# circuit.net
KiCad netlist of a schematic drawn in EAGLE
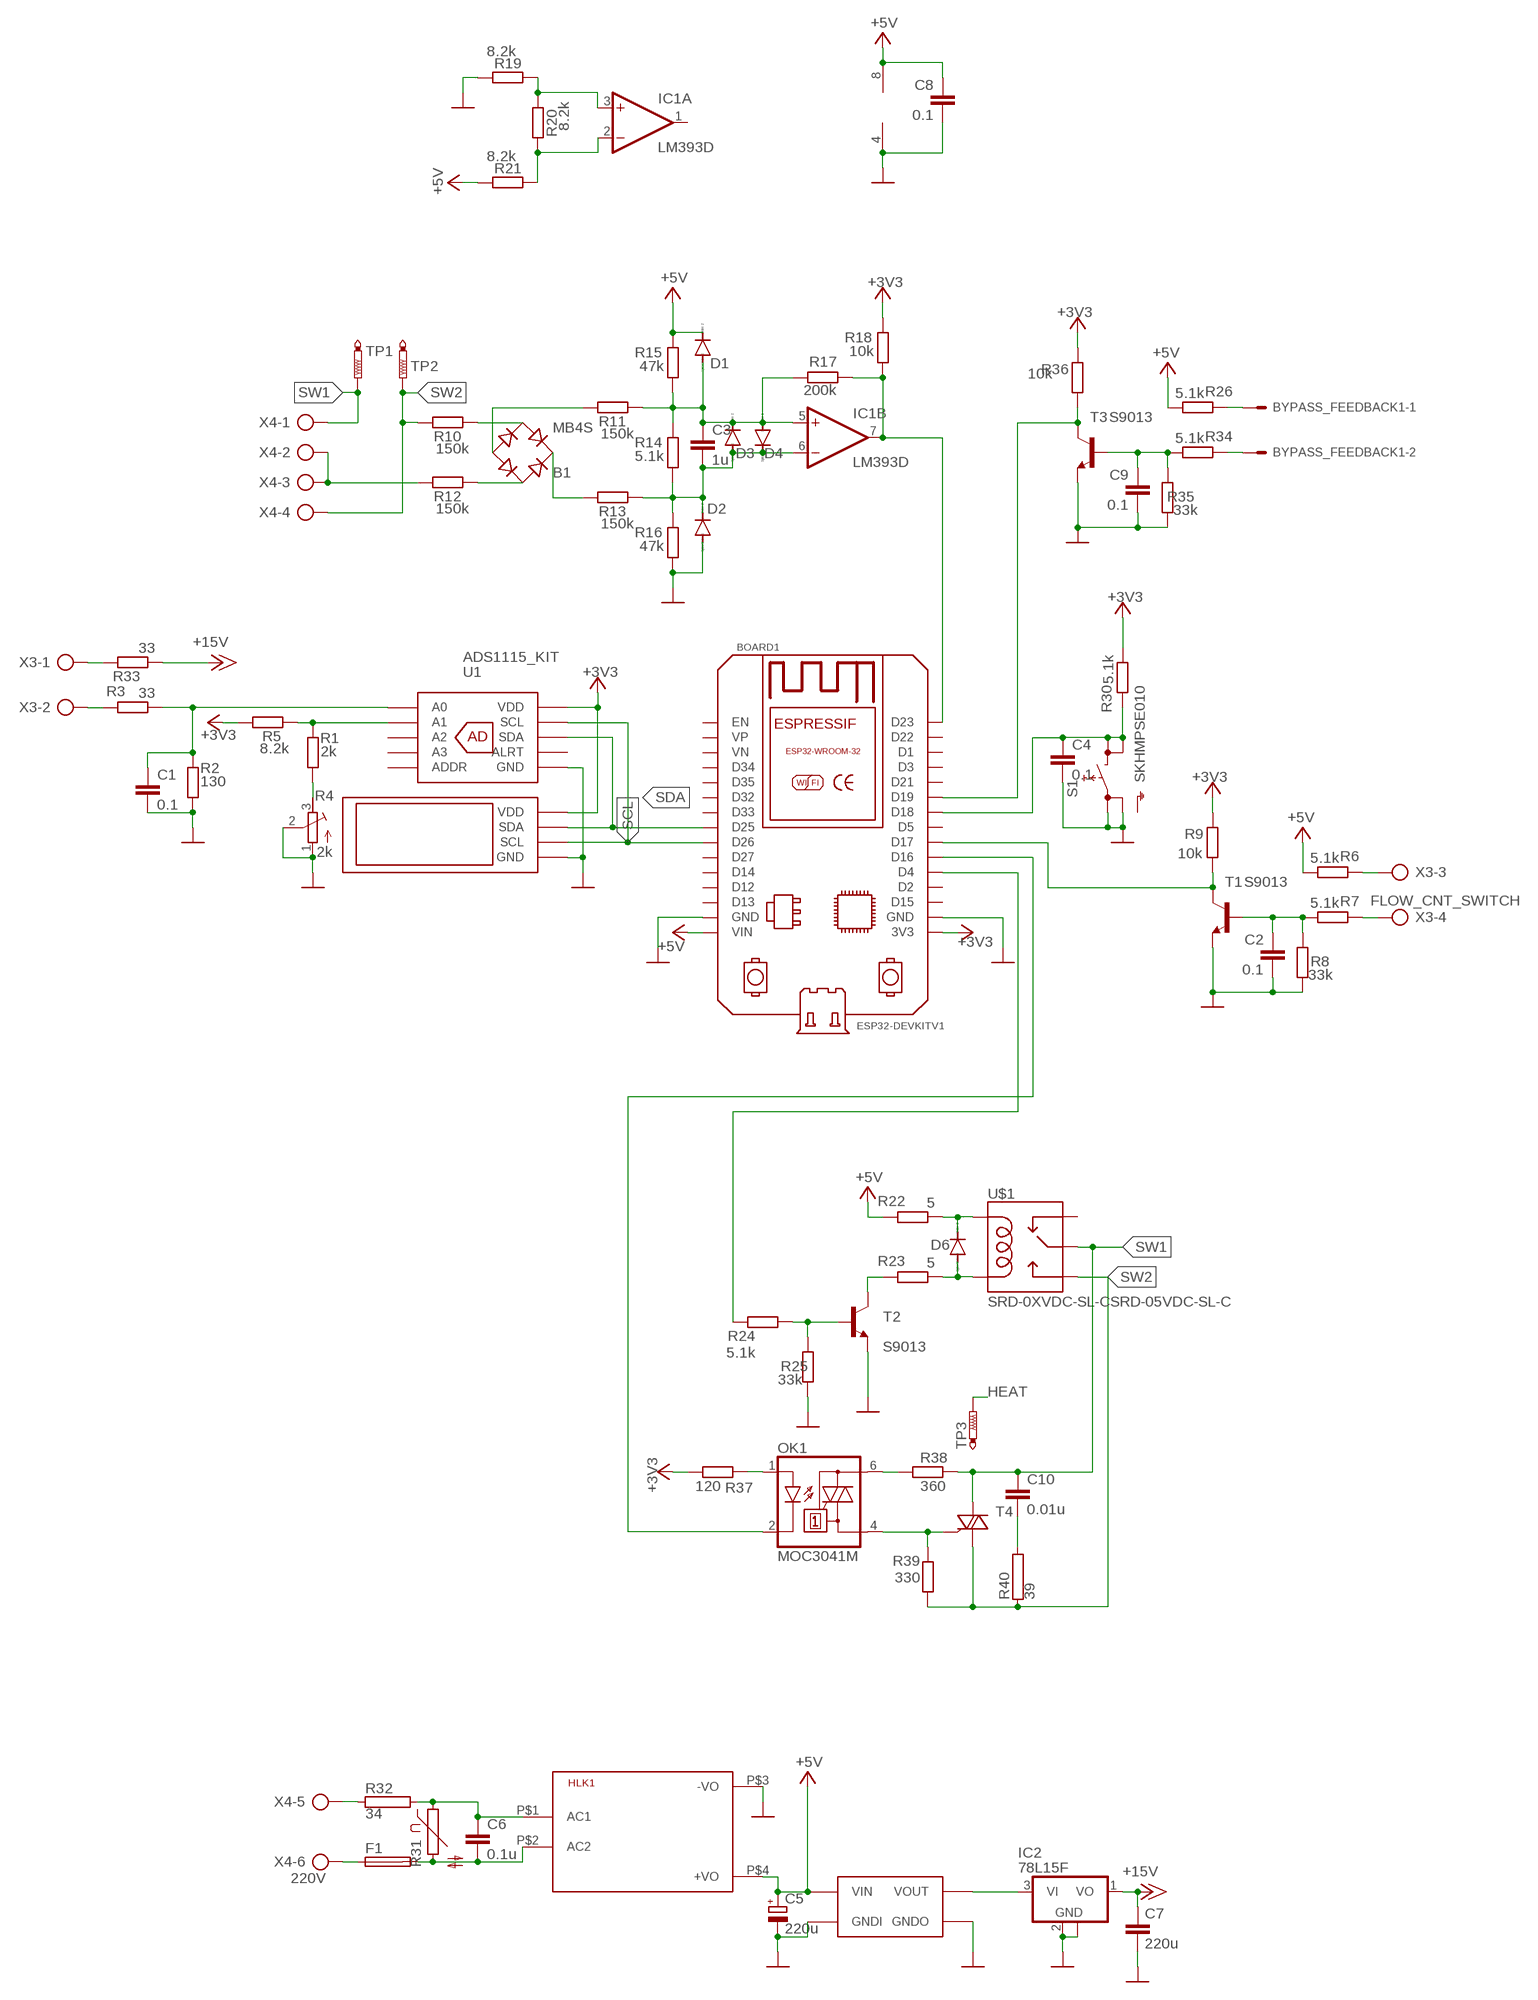
[diagram p0: schematic, sheet 1]

(export (version "E")
  (design (tool "Eeschema 10.0.6"))
  (components
    (comp (ref "B1")
      (value "MB4S")
      (footprint "eagle-import:SOIC-4")
      (libsource (lib "eagle-import") (part "MBS4"))
    )
    (comp (ref "BOARD1")
      (value "ESP32DEVKITV1")
      (footprint "eagle-import:ESP32-DEVKITV1")
      (libsource (lib "eagle-import") (part "ESP32DEVKITV1"))
    )
    (comp (ref "BYPASS_FEEDBACK1")
      (value "C-GRID-02-70543")
      (footprint "eagle-import:70543-02")
      (fields (field (name "MF") "MOLEX"))
      (libsource (lib "eagle-import") (part "C-GRID-02-70543"))
    )
    (comp (ref "C1")
      (value "0.1")
      (footprint "eagle-import:C1206")
      (libsource (lib "eagle-import") (part "C-EUC1206"))
    )
    (comp (ref "C2")
      (value "0.1")
      (footprint "eagle-import:C1206")
      (libsource (lib "eagle-import") (part "C-EUC1206"))
    )
    (comp (ref "C3")
      (value "1u")
      (footprint "eagle-import:C1206")
      (libsource (lib "eagle-import") (part "C-EUC1206"))
    )
    (comp (ref "C4")
      (value "0.1")
      (footprint "eagle-import:C1206")
      (libsource (lib "eagle-import") (part "C-EUC1206"))
    )
    (comp (ref "C5")
      (value "220u")
      (footprint "eagle-import:E3,5-8")
      (libsource (lib "eagle-import") (part "CPOL-EUE3.5-8"))
    )
    (comp (ref "C6")
      (value "0.1u")
      (footprint "eagle-import:C10B5")
      (libsource (lib "eagle-import") (part "C10/5"))
    )
    (comp (ref "C7")
      (value "220u")
      (footprint "eagle-import:C1210K")
      (libsource (lib "eagle-import") (part "C-EUC1210K"))
    )
    (comp (ref "C8")
      (value "0.1")
      (footprint "eagle-import:C1206")
      (libsource (lib "eagle-import") (part "C-EUC1206"))
    )
    (comp (ref "C9")
      (value "0.1")
      (footprint "eagle-import:C1206")
      (libsource (lib "eagle-import") (part "C-EUC1206"))
    )
    (comp (ref "C10")
      (value "0.01u")
      (footprint "eagle-import:C10B5")
      (libsource (lib "eagle-import") (part "C10/5"))
    )
    (comp (ref "D1")
      (value "CGRM4001-G")
      (footprint "eagle-import:SOD-123_MINI-SMA")
      (libsource (lib "eagle-import") (part "CGRM400-G1"))
    )
    (comp (ref "D2")
      (value "CGRM4001-G")
      (footprint "eagle-import:SOD-123_MINI-SMA")
      (libsource (lib "eagle-import") (part "CGRM400-G1"))
    )
    (comp (ref "D3")
      (value "CGRM4001-G")
      (footprint "eagle-import:SOD-123_MINI-SMA")
      (libsource (lib "eagle-import") (part "CGRM400-G1"))
    )
    (comp (ref "D4")
      (value "CGRM4001-G")
      (footprint "eagle-import:SOD-123_MINI-SMA")
      (libsource (lib "eagle-import") (part "CGRM400-G1"))
    )
    (comp (ref "D6")
      (value "CGRM4001-G")
      (footprint "eagle-import:SOD-123_MINI-SMA")
      (libsource (lib "eagle-import") (part "CGRM400-G1"))
    )
    (comp (ref "DC1")
      (value "HW-668_DC_DC_STEPUP")
      (footprint "eagle-import:HW-668_DC_DC_STEPUP")
      (libsource (lib "eagle-import") (part "HW-668_DC_DC_STEPUP"))
    )
    (comp (ref "F1")
      (value "FUSE19560")
      (footprint "eagle-import:19560")
      (fields (field (name "MPN") "56000001009"))
      (libsource (lib "eagle-import") (part "FUSE19560"))
    )
    (comp (ref "HLK1")
      (value "HLK-PM013W")
      (footprint "eagle-import:HLK-PM01")
      (libsource (lib "eagle-import") (part "HLK-PM013W"))
    )
    (comp (ref "IC1")
      (value "LM393D")
      (footprint "eagle-import:SO08")
      (libsource (lib "eagle-import") (part "LM393D"))
    )
    (comp (ref "IC2")
      (value "78L15F")
      (footprint "eagle-import:SOT89")
      (libsource (lib "eagle-import") (part "78LF15"))
    )
    (comp (ref "OK1")
      (value "MOC3041M")
      (footprint "eagle-import:DIL06")
      (fields (field (name "MF") "FAIRCHILD SEMICONDUCTOR"))
      (libsource (lib "eagle-import") (part "MOC3041M"))
    )
    (comp (ref "R1")
      (value "2k")
      (footprint "eagle-import:R1206")
      (libsource (lib "eagle-import") (part "R-EU_R1206"))
    )
    (comp (ref "R2")
      (value "130")
      (footprint "eagle-import:R1206")
      (libsource (lib "eagle-import") (part "R-EU_R1206"))
    )
    (comp (ref "R3")
      (value "33")
      (footprint "eagle-import:R1206")
      (libsource (lib "eagle-import") (part "R-EU_R1206"))
    )
    (comp (ref "R4")
      (value "2k")
      (footprint "eagle-import:RTRIM3202")
      (libsource (lib "eagle-import") (part "R-TRIMM3202"))
    )
    (comp (ref "R5")
      (value "8.2k")
      (footprint "eagle-import:R1206")
      (libsource (lib "eagle-import") (part "R-EU_R1206"))
    )
    (comp (ref "R6")
      (value "5.1k")
      (footprint "eagle-import:R1206")
      (libsource (lib "eagle-import") (part "R-EU_R1206"))
    )
    (comp (ref "R7")
      (value "5.1k")
      (footprint "eagle-import:R1206")
      (libsource (lib "eagle-import") (part "R-EU_R1206"))
    )
    (comp (ref "R8")
      (value "33k")
      (footprint "eagle-import:R1206")
      (libsource (lib "eagle-import") (part "R-EU_R1206"))
    )
    (comp (ref "R9")
      (value "10k")
      (footprint "eagle-import:R1206")
      (libsource (lib "eagle-import") (part "R-EU_R1206"))
    )
    (comp (ref "R10")
      (value "150k")
      (footprint "eagle-import:R1206")
      (libsource (lib "eagle-import") (part "R-EU_R1206"))
    )
    (comp (ref "R11")
      (value "150k")
      (footprint "eagle-import:R1206")
      (libsource (lib "eagle-import") (part "R-EU_R1206"))
    )
    (comp (ref "R12")
      (value "150k")
      (footprint "eagle-import:R1206")
      (libsource (lib "eagle-import") (part "R-EU_R1206"))
    )
    (comp (ref "R13")
      (value "150k")
      (footprint "eagle-import:R1206")
      (libsource (lib "eagle-import") (part "R-EU_R1206"))
    )
    (comp (ref "R14")
      (value "5.1k")
      (footprint "eagle-import:R1206")
      (libsource (lib "eagle-import") (part "R-EU_R1206"))
    )
    (comp (ref "R15")
      (value "47k")
      (footprint "eagle-import:R1206")
      (libsource (lib "eagle-import") (part "R-EU_R1206"))
    )
    (comp (ref "R16")
      (value "47k")
      (footprint "eagle-import:R1206")
      (libsource (lib "eagle-import") (part "R-EU_R1206"))
    )
    (comp (ref "R17")
      (value "200k")
      (footprint "eagle-import:R1206")
      (libsource (lib "eagle-import") (part "R-EU_R1206"))
    )
    (comp (ref "R18")
      (value "10k")
      (footprint "eagle-import:R1206")
      (libsource (lib "eagle-import") (part "R-EU_R1206"))
    )
    (comp (ref "R19")
      (value "8.2k")
      (footprint "eagle-import:R1206")
      (libsource (lib "eagle-import") (part "R-EU_R1206"))
    )
    (comp (ref "R20")
      (value "8.2k")
      (footprint "eagle-import:R1206")
      (libsource (lib "eagle-import") (part "R-EU_R1206"))
    )
    (comp (ref "R21")
      (value "8.2k")
      (footprint "eagle-import:R1206")
      (libsource (lib "eagle-import") (part "R-EU_R1206"))
    )
    (comp (ref "R22")
      (value "5")
      (footprint "eagle-import:R1206")
      (libsource (lib "eagle-import") (part "R-EU_R1206"))
    )
    (comp (ref "R23")
      (value "5")
      (footprint "eagle-import:R1206")
      (libsource (lib "eagle-import") (part "R-EU_R1206"))
    )
    (comp (ref "R24")
      (value "5.1k")
      (footprint "eagle-import:R1206")
      (libsource (lib "eagle-import") (part "R-EU_R1206"))
    )
    (comp (ref "R25")
      (value "33k")
      (footprint "eagle-import:R1206")
      (libsource (lib "eagle-import") (part "R-EU_R1206"))
    )
    (comp (ref "R26")
      (value "5.1k")
      (footprint "eagle-import:R1206")
      (libsource (lib "eagle-import") (part "R-EU_R1206"))
    )
    (comp (ref "R30")
      (value "5.1k")
      (footprint "eagle-import:R1206")
      (libsource (lib "eagle-import") (part "R-EU_R1206"))
    )
    (comp (ref "R31")
      (value "S10K510")
      (footprint "eagle-import:S10K510")
      (libsource (lib "eagle-import") (part "S10K510"))
    )
    (comp (ref "R32")
      (value "34")
      (footprint "eagle-import:CA0001")
      (libsource (lib "eagle-import") (part "RCA0001"))
    )
    (comp (ref "R33")
      (value "33")
      (footprint "eagle-import:R1206")
      (libsource (lib "eagle-import") (part "R-EU_R1206"))
    )
    (comp (ref "R34")
      (value "5.1k")
      (footprint "eagle-import:R1206")
      (libsource (lib "eagle-import") (part "R-EU_R1206"))
    )
    (comp (ref "R35")
      (value "33k")
      (footprint "eagle-import:R1206")
      (libsource (lib "eagle-import") (part "R-EU_R1206"))
    )
    (comp (ref "R36")
      (value "10k")
      (footprint "eagle-import:R1206")
      (libsource (lib "eagle-import") (part "R-EU_R1206"))
    )
    (comp (ref "R37")
      (value "120")
      (footprint "eagle-import:R1206")
      (libsource (lib "eagle-import") (part "R-EU_R1206"))
    )
    (comp (ref "R38")
      (value "360")
      (footprint "eagle-import:R1206")
      (libsource (lib "eagle-import") (part "R-EU_R1206"))
    )
    (comp (ref "R39")
      (value "330")
      (footprint "eagle-import:R1206")
      (libsource (lib "eagle-import") (part "R-EU_R1206"))
    )
    (comp (ref "R40")
      (value "39")
      (footprint "eagle-import:CA0001")
      (libsource (lib "eagle-import") (part "RCA0001"))
    )
    (comp (ref "S1")
      (value "SKHMPSE010")
      (footprint "eagle-import:SKHMPXE010")
      (libsource (lib "eagle-import") (part "SKHMPE010S"))
    )
    (comp (ref "T1")
      (value "S9013")
      (footprint "eagle-import:SOT23-BEC")
      (libsource (lib "eagle-import") (part "-NPN-SOT23-BECBC808"))
    )
    (comp (ref "T2")
      (value "S9013")
      (footprint "eagle-import:SOT23-BEC")
      (libsource (lib "eagle-import") (part "-NPN-SOT23-BECBC808"))
    )
    (comp (ref "T3")
      (value "S9013")
      (footprint "eagle-import:SOT23-BEC")
      (libsource (lib "eagle-import") (part "-NPN-SOT23-BECBC808"))
    )
    (comp (ref "T4")
      (value "BT136")
      (footprint "eagle-import:TO220AB")
      (libsource (lib "eagle-import") (part "BT136"))
    )
    (comp (ref "TP1")
      (value "PTR1PAD1-20Y")
      (footprint "eagle-import:P1-20Y")
      (libsource (lib "eagle-import") (part "PTR1PAD1-20Y"))
    )
    (comp (ref "TP2")
      (value "PTR1PAD1-20Y")
      (footprint "eagle-import:P1-20Y")
      (libsource (lib "eagle-import") (part "PTR1PAD1-20Y"))
    )
    (comp (ref "TP3")
      (value "PTR1B1,27")
      (footprint "eagle-import:B1,27")
      (libsource (lib "eagle-import") (part "PTR1B1,27"))
    )
    (comp (ref "U$1")
      (value "SRD-0XVDC-SL-CSRD-05VDC-SL-C")
      (footprint "eagle-import:SRD-0XVDC-SL-C")
      (libsource (lib "eagle-import") (part "SRD-0XVDC-SL-CSRD-05VDC-SL-C"))
    )
    (comp (ref "U1")
      (value "ADS1115_KIT")
      (footprint "eagle-import:ADS1115_KIT")
      (libsource (lib "eagle-import") (part "ADS1115_KIT"))
    )
    (comp (ref "U2")
      (value "SSD1306_OLED")
      (footprint "eagle-import:SSD1306_OLED")
      (libsource (lib "eagle-import") (part "SSD1306_OLED"))
    )
    (comp (ref "X3")
      (value "FLOW_CNT_SWITCH")
      (footprint "eagle-import:AK300_4")
      (libsource (lib "eagle-import") (part "AK300/4"))
    )
    (comp (ref "X4")
      (value "220V")
      (footprint "eagle-import:AK300_6")
      (libsource (lib "eagle-import") (part "AK300/6"))
    )
  )
  (nets
    (net (code "1") (name "+3V3") (class "Default")
      (node (ref "BOARD1") (pin "3V3") (pinfunction "3V3_3V3") (pintype "bidirectional"))
      (node (ref "R18") (pin "1") (pinfunction "1_1") (pintype "passive"))
      (node (ref "R30") (pin "1") (pinfunction "1_1") (pintype "passive"))
      (node (ref "R36") (pin "1") (pinfunction "1_1") (pintype "passive"))
      (node (ref "R37") (pin "1") (pinfunction "1_1") (pintype "passive"))
      (node (ref "R5") (pin "2") (pinfunction "2_2") (pintype "passive"))
      (node (ref "R9") (pin "1") (pinfunction "1_1") (pintype "passive"))
      (node (ref "U1") (pin "P$1") (pinfunction "VDD_P$1") (pintype "power_in"))
      (node (ref "U2") (pin "P$3") (pinfunction "VDD_P$3") (pintype "power_in"))
    )
    (net (code "2") (name "+5V") (class "Default")
      (node (ref "BOARD1") (pin "VIN") (pinfunction "VIN_VIN") (pintype "bidirectional"))
      (node (ref "C5") (pin "+") (pinfunction "+_+") (pintype "passive"))
      (node (ref "C8") (pin "1") (pinfunction "1_1") (pintype "passive"))
      (node (ref "D1") (pin "C") (pinfunction "C_C") (pintype "passive"))
      (node (ref "DC1") (pin "P$1") (pinfunction "VIN_P$1") (pintype "power_in"))
      (node (ref "HLK1") (pin "P$4") (pinfunction "+VO_P$4") (pintype "bidirectional"))
      (node (ref "IC1") (pin "8") (pinfunction "V+_8") (pintype "power_in"))
      (node (ref "R15") (pin "1") (pinfunction "1_1") (pintype "passive"))
      (node (ref "R21") (pin "1") (pinfunction "1_1") (pintype "passive"))
      (node (ref "R22") (pin "2") (pinfunction "2_2") (pintype "passive"))
      (node (ref "R26") (pin "1") (pinfunction "1_1") (pintype "passive"))
      (node (ref "R6") (pin "1") (pinfunction "1_1") (pintype "passive"))
    )
    (net (code "3") (name "+15V") (class "Default")
      (node (ref "C7") (pin "1") (pinfunction "1_1") (pintype "passive"))
      (node (ref "IC2") (pin "1") (pinfunction "VO_1") (pintype "passive"))
      (node (ref "R33") (pin "1") (pinfunction "1_1") (pintype "passive"))
    )
    (net (code "4") (name "/HEAT") (class "Default")
      (node (ref "TP3") (pin "TP") (pinfunction "TP_TP") (pintype "input"))
    )
    (net (code "5") (name "GND") (class "Default")
      (node (ref "BOARD1") (pin "GND") (pinfunction "GND_GND") (pintype "bidirectional"))
      (node (ref "BOARD1") (pin "GND@1") (pinfunction "GND_GND@1") (pintype "bidirectional"))
      (node (ref "C1") (pin "2") (pinfunction "2_2") (pintype "passive"))
      (node (ref "C2") (pin "2") (pinfunction "2_2") (pintype "passive"))
      (node (ref "C4") (pin "2") (pinfunction "2_2") (pintype "passive"))
      (node (ref "C5") (pin "-") (pinfunction "-_-") (pintype "passive"))
      (node (ref "C7") (pin "2") (pinfunction "2_2") (pintype "passive"))
      (node (ref "C8") (pin "2") (pinfunction "2_2") (pintype "passive"))
      (node (ref "C9") (pin "2") (pinfunction "2_2") (pintype "passive"))
      (node (ref "D2") (pin "A") (pinfunction "A_A") (pintype "passive"))
      (node (ref "DC1") (pin "P$2") (pinfunction "GNDI_P$2") (pintype "power_in"))
      (node (ref "DC1") (pin "P$3") (pinfunction "GNDO_P$3") (pintype "power_in"))
      (node (ref "HLK1") (pin "P$3") (pinfunction "-VO_P$3") (pintype "bidirectional"))
      (node (ref "IC1") (pin "4") (pinfunction "V-_4") (pintype "power_in"))
      (node (ref "IC2") (pin "2") (pinfunction "GND_2") (pintype "passive"))
      (node (ref "IC2") (pin "2@1") (pinfunction "GND_2@1") (pintype "passive"))
      (node (ref "R16") (pin "2") (pinfunction "2_2") (pintype "passive"))
      (node (ref "R19") (pin "1") (pinfunction "1_1") (pintype "passive"))
      (node (ref "R2") (pin "1") (pinfunction "1_1") (pintype "passive"))
      (node (ref "R25") (pin "2") (pinfunction "2_2") (pintype "passive"))
      (node (ref "R35") (pin "2") (pinfunction "2_2") (pintype "passive"))
      (node (ref "R4") (pin "1") (pinfunction "A_1") (pintype "passive"))
      (node (ref "R4") (pin "2") (pinfunction "S_2") (pintype "passive"))
      (node (ref "R8") (pin "2") (pinfunction "2_2") (pintype "passive"))
      (node (ref "S1") (pin "1") (pinfunction "1.1_1") (pintype "passive"))
      (node (ref "S1") (pin "2") (pinfunction "1.2_2") (pintype "passive"))
      (node (ref "T1") (pin "E") (pinfunction "E_E") (pintype "passive"))
      (node (ref "T2") (pin "E") (pinfunction "E_E") (pintype "passive"))
      (node (ref "T3") (pin "E") (pinfunction "E_E") (pintype "passive"))
      (node (ref "U1") (pin "P$2") (pinfunction "GND_P$2") (pintype "power_in"))
      (node (ref "U2") (pin "P$4") (pinfunction "GND_P$4") (pintype "power_in"))
    )
    (net (code "6") (name "Net-(B1-AC1)") (class "Default")
      (node (ref "B1") (pin "~1") (pinfunction "AC1_~1") (pintype "passive"))
      (node (ref "R12") (pin "1") (pinfunction "1_1") (pintype "passive"))
    )
    (net (code "7") (name "Net-(B1-AC2)") (class "Default")
      (node (ref "B1") (pin "~2") (pinfunction "AC2_~2") (pintype "passive"))
      (node (ref "R10") (pin "1") (pinfunction "1_1") (pintype "passive"))
    )
    (net (code "8") (name "Net-(B1-Pad+)") (class "Default")
      (node (ref "B1") (pin "+") (pinfunction "+_+") (pintype "passive"))
      (node (ref "R13") (pin "2") (pinfunction "2_2") (pintype "passive"))
    )
    (net (code "9") (name "Net-(B1-Pad-)") (class "Default")
      (node (ref "B1") (pin "-") (pinfunction "-_-") (pintype "passive"))
      (node (ref "R11") (pin "2") (pinfunction "2_2") (pintype "passive"))
    )
    (net (code "10") (name "Net-(BOARD1-PadD4)") (class "Default")
      (node (ref "BOARD1") (pin "D4") (pinfunction "D4_D4") (pintype "bidirectional"))
      (node (ref "R24") (pin "2") (pinfunction "2_2") (pintype "passive"))
    )
    (net (code "11") (name "Net-(BOARD1-PadD17)") (class "Default")
      (node (ref "BOARD1") (pin "D17") (pinfunction "D17_D17") (pintype "bidirectional"))
      (node (ref "R9") (pin "2") (pinfunction "2_2") (pintype "passive"))
      (node (ref "T1") (pin "C") (pinfunction "C_C") (pintype "passive"))
    )
    (net (code "12") (name "Net-(BOARD1-PadD19)") (class "Default")
      (node (ref "BOARD1") (pin "D19") (pinfunction "D19_D19") (pintype "bidirectional"))
      (node (ref "R36") (pin "2") (pinfunction "2_2") (pintype "passive"))
      (node (ref "T3") (pin "C") (pinfunction "C_C") (pintype "passive"))
    )
    (net (code "13") (name "Net-(BYPASS_FEEDBACK1A-S)") (class "Default")
      (node (ref "BYPASS_FEEDBACK1") (pin "1") (pinfunction "S_1") (pintype "passive"))
      (node (ref "R26") (pin "2") (pinfunction "2_2") (pintype "passive"))
    )
    (net (code "14") (name "Net-(BYPASS_FEEDBACK1B-S)") (class "Default")
      (node (ref "BYPASS_FEEDBACK1") (pin "2") (pinfunction "S_2") (pintype "passive"))
      (node (ref "R34") (pin "2") (pinfunction "2_2") (pintype "passive"))
    )
    (net (code "15") (name "Net-(C2-Pad1)") (class "Default")
      (node (ref "C2") (pin "1") (pinfunction "1_1") (pintype "passive"))
      (node (ref "R7") (pin "1") (pinfunction "1_1") (pintype "passive"))
      (node (ref "R8") (pin "1") (pinfunction "1_1") (pintype "passive"))
      (node (ref "T1") (pin "B") (pinfunction "B_B") (pintype "passive"))
    )
    (net (code "16") (name "Net-(C9-Pad1)") (class "Default")
      (node (ref "C9") (pin "1") (pinfunction "1_1") (pintype "passive"))
      (node (ref "R34") (pin "1") (pinfunction "1_1") (pintype "passive"))
      (node (ref "R35") (pin "1") (pinfunction "1_1") (pintype "passive"))
      (node (ref "T3") (pin "B") (pinfunction "B_B") (pintype "passive"))
    )
    (net (code "17") (name "Net-(C10-Pad2)") (class "Default")
      (node (ref "C10") (pin "2") (pinfunction "2_2") (pintype "passive"))
      (node (ref "R40") (pin "2") (pinfunction "2_2") (pintype "passive"))
    )
    (net (code "18") (name "Net-(D6-PadA)") (class "Default")
      (node (ref "D6") (pin "A") (pinfunction "A_A") (pintype "passive"))
      (node (ref "R23") (pin "1") (pinfunction "1_1") (pintype "passive"))
      (node (ref "U$1") (pin "COIL0") (pinfunction "COIL0_COIL0") (pintype "bidirectional"))
    )
    (net (code "19") (name "Net-(D6-PadC)") (class "Default")
      (node (ref "D6") (pin "C") (pinfunction "C_C") (pintype "passive"))
      (node (ref "R22") (pin "1") (pinfunction "1_1") (pintype "passive"))
      (node (ref "U$1") (pin "COIL1") (pinfunction "COIL1_COIL1") (pintype "bidirectional"))
    )
    (net (code "20") (name "Net-(DC1-VOUT)") (class "Default")
      (node (ref "DC1") (pin "P$4") (pinfunction "VOUT_P$4") (pintype "power_in"))
      (node (ref "IC2") (pin "3") (pinfunction "VI_3") (pintype "input"))
    )
    (net (code "21") (name "Net-(HLK1-AC1)") (class "Default")
      (node (ref "C6") (pin "1") (pinfunction "1_1") (pintype "passive"))
      (node (ref "HLK1") (pin "P$1") (pinfunction "AC1_P$1") (pintype "bidirectional"))
      (node (ref "R31") (pin "1") (pinfunction "1_1") (pintype "passive"))
      (node (ref "R32") (pin "2") (pinfunction "2_2") (pintype "passive"))
    )
    (net (code "22") (name "Net-(HLK1-AC2)") (class "Default")
      (node (ref "C6") (pin "2") (pinfunction "2_2") (pintype "passive"))
      (node (ref "F1") (pin "2") (pinfunction "2_2") (pintype "passive"))
      (node (ref "HLK1") (pin "P$2") (pinfunction "AC2_P$2") (pintype "bidirectional"))
      (node (ref "R31") (pin "2") (pinfunction "2_2") (pintype "passive"))
    )
    (net (code "23") (name "Net-(IC1A-+IN)") (class "Default")
      (node (ref "IC1") (pin "3") (pinfunction "+IN_3") (pintype "input"))
      (node (ref "R19") (pin "2") (pinfunction "2_2") (pintype "passive"))
      (node (ref "R20") (pin "1") (pinfunction "1_1") (pintype "passive"))
    )
    (net (code "24") (name "Net-(IC1A--IN)") (class "Default")
      (node (ref "IC1") (pin "2") (pinfunction "-IN_2") (pintype "input"))
      (node (ref "R20") (pin "2") (pinfunction "2_2") (pintype "passive"))
      (node (ref "R21") (pin "2") (pinfunction "2_2") (pintype "passive"))
    )
    (net (code "25") (name "Net-(IC1B-+IN)") (class "Default")
      (node (ref "C3") (pin "1") (pinfunction "1_1") (pintype "passive"))
      (node (ref "D1") (pin "A") (pinfunction "A_A") (pintype "passive"))
      (node (ref "D3") (pin "C") (pinfunction "C_C") (pintype "passive"))
      (node (ref "D4") (pin "A") (pinfunction "A_A") (pintype "passive"))
      (node (ref "IC1") (pin "5") (pinfunction "+IN_5") (pintype "input"))
      (node (ref "R11") (pin "1") (pinfunction "1_1") (pintype "passive"))
      (node (ref "R14") (pin "1") (pinfunction "1_1") (pintype "passive"))
      (node (ref "R15") (pin "2") (pinfunction "2_2") (pintype "passive"))
      (node (ref "R17") (pin "1") (pinfunction "1_1") (pintype "passive"))
    )
    (net (code "26") (name "Net-(IC1B--IN)") (class "Default")
      (node (ref "C3") (pin "2") (pinfunction "2_2") (pintype "passive"))
      (node (ref "D2") (pin "C") (pinfunction "C_C") (pintype "passive"))
      (node (ref "D3") (pin "A") (pinfunction "A_A") (pintype "passive"))
      (node (ref "D4") (pin "C") (pinfunction "C_C") (pintype "passive"))
      (node (ref "IC1") (pin "6") (pinfunction "-IN_6") (pintype "input"))
      (node (ref "R13") (pin "1") (pinfunction "1_1") (pintype "passive"))
      (node (ref "R14") (pin "2") (pinfunction "2_2") (pintype "passive"))
      (node (ref "R16") (pin "1") (pinfunction "1_1") (pintype "passive"))
    )
    (net (code "27") (name "Net-(IC1B-OUT)") (class "Default")
      (node (ref "BOARD1") (pin "D23") (pinfunction "D23_D23") (pintype "bidirectional"))
      (node (ref "IC1") (pin "7") (pinfunction "OUT_7") (pintype "output"))
      (node (ref "R17") (pin "2") (pinfunction "2_2") (pintype "passive"))
      (node (ref "R18") (pin "2") (pinfunction "2_2") (pintype "passive"))
    )
    (net (code "28") (name "Net-(OK1-A)") (class "Default")
      (node (ref "OK1") (pin "1") (pinfunction "A_1") (pintype "passive"))
      (node (ref "R37") (pin "2") (pinfunction "2_2") (pintype "passive"))
    )
    (net (code "29") (name "Net-(OK1-A1)") (class "Default")
      (node (ref "OK1") (pin "4") (pinfunction "A1_4") (pintype "passive"))
      (node (ref "R39") (pin "2") (pinfunction "2_2") (pintype "passive"))
      (node (ref "T4") (pin "3") (pinfunction "G_3") (pintype "passive"))
    )
    (net (code "30") (name "Net-(OK1-A2)") (class "Default")
      (node (ref "OK1") (pin "6") (pinfunction "A2_6") (pintype "passive"))
      (node (ref "R38") (pin "1") (pinfunction "1_1") (pintype "passive"))
    )
    (net (code "31") (name "Net-(OK1-C)") (class "Default")
      (node (ref "BOARD1") (pin "D16") (pinfunction "D16_D16") (pintype "bidirectional"))
      (node (ref "OK1") (pin "2") (pinfunction "C_2") (pintype "passive"))
    )
    (net (code "32") (name "Net-(R4-E)") (class "Default")
      (node (ref "R1") (pin "1") (pinfunction "1_1") (pintype "passive"))
      (node (ref "R4") (pin "3") (pinfunction "E_3") (pintype "passive"))
    )
    (net (code "33") (name "Net-(R23-Pad2)") (class "Default")
      (node (ref "R23") (pin "2") (pinfunction "2_2") (pintype "passive"))
      (node (ref "T2") (pin "C") (pinfunction "C_C") (pintype "passive"))
    )
    (net (code "34") (name "Net-(R24-Pad1)") (class "Default")
      (node (ref "R24") (pin "1") (pinfunction "1_1") (pintype "passive"))
      (node (ref "R25") (pin "1") (pinfunction "1_1") (pintype "passive"))
      (node (ref "T2") (pin "B") (pinfunction "B_B") (pintype "passive"))
    )
    (net (code "35") (name "Net-(S1-2.1)") (class "Default")
      (node (ref "BOARD1") (pin "D18") (pinfunction "D18_D18") (pintype "bidirectional"))
      (node (ref "C4") (pin "1") (pinfunction "1_1") (pintype "passive"))
      (node (ref "R30") (pin "2") (pinfunction "2_2") (pintype "passive"))
      (node (ref "S1") (pin "3") (pinfunction "2.1_3") (pintype "passive"))
      (node (ref "S1") (pin "4") (pinfunction "2.2_4") (pintype "passive"))
    )
    (net (code "36") (name "Net-(U1-A0)") (class "Default")
      (node (ref "C1") (pin "1") (pinfunction "1_1") (pintype "passive"))
      (node (ref "R2") (pin "2") (pinfunction "2_2") (pintype "passive"))
      (node (ref "R3") (pin "1") (pinfunction "1_1") (pintype "passive"))
      (node (ref "U1") (pin "P$7") (pinfunction "A0_P$7") (pintype "input"))
    )
    (net (code "37") (name "Net-(U1-A1)") (class "Default")
      (node (ref "R1") (pin "2") (pinfunction "2_2") (pintype "passive"))
      (node (ref "R5") (pin "1") (pinfunction "1_1") (pintype "passive"))
      (node (ref "U1") (pin "P$8") (pinfunction "A1_P$8") (pintype "input"))
    )
    (net (code "38") (name "Net-(X3A-KL)") (class "Default")
      (node (ref "R33") (pin "2") (pinfunction "2_2") (pintype "passive"))
      (node (ref "X3") (pin "1") (pinfunction "KL_1") (pintype "passive"))
    )
    (net (code "39") (name "Net-(X3B-KL)") (class "Default")
      (node (ref "R3") (pin "2") (pinfunction "2_2") (pintype "passive"))
      (node (ref "X3") (pin "2") (pinfunction "KL_2") (pintype "passive"))
    )
    (net (code "40") (name "Net-(X3C-KL)") (class "Default")
      (node (ref "R6") (pin "2") (pinfunction "2_2") (pintype "passive"))
      (node (ref "X3") (pin "3") (pinfunction "KL_3") (pintype "passive"))
    )
    (net (code "41") (name "Net-(X3D-KL)") (class "Default")
      (node (ref "R7") (pin "2") (pinfunction "2_2") (pintype "passive"))
      (node (ref "X3") (pin "4") (pinfunction "KL_4") (pintype "passive"))
    )
    (net (code "42") (name "Net-(X4B-KL)") (class "Default")
      (node (ref "R12") (pin "2") (pinfunction "2_2") (pintype "passive"))
      (node (ref "X4") (pin "2") (pinfunction "KL_2") (pintype "passive"))
      (node (ref "X4") (pin "3") (pinfunction "KL_3") (pintype "passive"))
    )
    (net (code "43") (name "Net-(X4E-KL)") (class "Default")
      (node (ref "R32") (pin "1") (pinfunction "1_1") (pintype "passive"))
      (node (ref "X4") (pin "5") (pinfunction "KL_5") (pintype "passive"))
    )
    (net (code "44") (name "Net-(X4F-KL)") (class "Default")
      (node (ref "F1") (pin "1") (pinfunction "1_1") (pintype "passive"))
      (node (ref "X4") (pin "6") (pinfunction "KL_6") (pintype "passive"))
    )
    (net (code "45") (name "SCL") (class "Default")
      (node (ref "BOARD1") (pin "D26") (pinfunction "D26_D26") (pintype "bidirectional"))
      (node (ref "U1") (pin "P$3") (pinfunction "SCL_P$3") (pintype "bidirectional"))
      (node (ref "U2") (pin "P$2") (pinfunction "SCL_P$2") (pintype "bidirectional"))
    )
    (net (code "46") (name "SDA") (class "Default")
      (node (ref "BOARD1") (pin "D25") (pinfunction "D25_D25") (pintype "bidirectional"))
      (node (ref "U1") (pin "P$4") (pinfunction "SDA_P$4") (pintype "bidirectional"))
      (node (ref "U2") (pin "P$1") (pinfunction "SDA_P$1") (pintype "bidirectional"))
    )
    (net (code "47") (name "SW1") (class "Default")
      (node (ref "C10") (pin "1") (pinfunction "1_1") (pintype "passive"))
      (node (ref "R38") (pin "2") (pinfunction "2_2") (pintype "passive"))
      (node (ref "T4") (pin "2") (pinfunction "A2_2") (pintype "passive"))
      (node (ref "TP1") (pin "TP") (pinfunction "TP_TP") (pintype "input"))
      (node (ref "U$1") (pin "SWCOMMON") (pinfunction "SWCOMMON_SWCOMMON") (pintype "bidirectional"))
      (node (ref "X4") (pin "1") (pinfunction "KL_1") (pintype "passive"))
    )
    (net (code "48") (name "SW2") (class "Default")
      (node (ref "R10") (pin "2") (pinfunction "2_2") (pintype "passive"))
      (node (ref "R39") (pin "1") (pinfunction "1_1") (pintype "passive"))
      (node (ref "R40") (pin "1") (pinfunction "1_1") (pintype "passive"))
      (node (ref "T4") (pin "1") (pinfunction "A1_1") (pintype "passive"))
      (node (ref "TP2") (pin "TP") (pinfunction "TP_TP") (pintype "input"))
      (node (ref "U$1") (pin "SWOPEN") (pinfunction "SWOPEN_SWOPEN") (pintype "bidirectional"))
      (node (ref "X4") (pin "4") (pinfunction "KL_4") (pintype "passive"))
    )
    (net (code "49") (name "unconnected-(BOARD1-PadD1)") (class "Default")
      (node (ref "BOARD1") (pin "D1") (pinfunction "D1_D1") (pintype "bidirectional"))
    )
    (net (code "50") (name "unconnected-(BOARD1-PadD2)") (class "Default")
      (node (ref "BOARD1") (pin "D2") (pinfunction "D2_D2") (pintype "bidirectional"))
    )
    (net (code "51") (name "unconnected-(BOARD1-PadD3)") (class "Default")
      (node (ref "BOARD1") (pin "D3") (pinfunction "D3_D3") (pintype "bidirectional"))
    )
    (net (code "52") (name "unconnected-(BOARD1-PadD5)") (class "Default")
      (node (ref "BOARD1") (pin "D5") (pinfunction "D5_D5") (pintype "bidirectional"))
    )
    (net (code "53") (name "unconnected-(BOARD1-PadD12)") (class "Default")
      (node (ref "BOARD1") (pin "D12") (pinfunction "D12_D12") (pintype "bidirectional"))
    )
    (net (code "54") (name "unconnected-(BOARD1-PadD13)") (class "Default")
      (node (ref "BOARD1") (pin "D13") (pinfunction "D13_D13") (pintype "bidirectional"))
    )
    (net (code "55") (name "unconnected-(BOARD1-PadD14)") (class "Default")
      (node (ref "BOARD1") (pin "D14") (pinfunction "D14_D14") (pintype "bidirectional"))
    )
    (net (code "56") (name "unconnected-(BOARD1-PadD15)") (class "Default")
      (node (ref "BOARD1") (pin "D15") (pinfunction "D15_D15") (pintype "bidirectional"))
    )
    (net (code "57") (name "unconnected-(BOARD1-PadD21)") (class "Default")
      (node (ref "BOARD1") (pin "D21") (pinfunction "D21_D21") (pintype "bidirectional"))
    )
    (net (code "58") (name "unconnected-(BOARD1-PadD22)") (class "Default")
      (node (ref "BOARD1") (pin "D22") (pinfunction "D22_D22") (pintype "bidirectional"))
    )
    (net (code "59") (name "unconnected-(BOARD1-PadD27)") (class "Default")
      (node (ref "BOARD1") (pin "D27") (pinfunction "D27_D27") (pintype "bidirectional"))
    )
    (net (code "60") (name "unconnected-(BOARD1-PadD32)") (class "Default")
      (node (ref "BOARD1") (pin "D32") (pinfunction "D32_D32") (pintype "bidirectional"))
    )
    (net (code "61") (name "unconnected-(BOARD1-PadD33)") (class "Default")
      (node (ref "BOARD1") (pin "D33") (pinfunction "D33_D33") (pintype "bidirectional"))
    )
    (net (code "62") (name "unconnected-(BOARD1-PadD34)") (class "Default")
      (node (ref "BOARD1") (pin "D34") (pinfunction "D34_D34") (pintype "bidirectional"))
    )
    (net (code "63") (name "unconnected-(BOARD1-PadD35)") (class "Default")
      (node (ref "BOARD1") (pin "D35") (pinfunction "D35_D35") (pintype "bidirectional"))
    )
    (net (code "64") (name "unconnected-(BOARD1-PadEN)") (class "Default")
      (node (ref "BOARD1") (pin "EN") (pinfunction "EN_EN") (pintype "bidirectional"))
    )
    (net (code "65") (name "unconnected-(BOARD1-PadVN)") (class "Default")
      (node (ref "BOARD1") (pin "VN") (pinfunction "VN_VN") (pintype "bidirectional"))
    )
    (net (code "66") (name "unconnected-(BOARD1-PadVP)") (class "Default")
      (node (ref "BOARD1") (pin "VP") (pinfunction "VP_VP") (pintype "bidirectional"))
    )
    (net (code "67") (name "unconnected-(IC1A-OUT-Pad1)") (class "Default")
      (node (ref "IC1") (pin "1") (pinfunction "OUT_1") (pintype "output"))
    )
    (net (code "68") (name "unconnected-(S1-SH-Pad5)") (class "Default")
      (node (ref "S1") (pin "5") (pinfunction "SH_5") (pintype "passive"))
    )
    (net (code "69") (name "unconnected-(U$1-SWCLOSE-PadSWCLOSED)") (class "Default")
      (node (ref "U$1") (pin "SWCLOSED") (pinfunction "SWCLOSE_SWCLOSED") (pintype "bidirectional"))
    )
    (net (code "70") (name "unconnected-(U1-A2-PadP$9)") (class "Default")
      (node (ref "U1") (pin "P$9") (pinfunction "A2_P$9") (pintype "input"))
    )
    (net (code "71") (name "unconnected-(U1-A3-PadP$10)") (class "Default")
      (node (ref "U1") (pin "P$10") (pinfunction "A3_P$10") (pintype "input"))
    )
    (net (code "72") (name "unconnected-(U1-ADDR-PadP$5)") (class "Default")
      (node (ref "U1") (pin "P$5") (pinfunction "ADDR_P$5") (pintype "input"))
    )
    (net (code "73") (name "unconnected-(U1-ALRT-PadP$6)") (class "Default")
      (node (ref "U1") (pin "P$6") (pinfunction "ALRT_P$6") (pintype "output"))
    )
  )
)
